# filterCard.net
KiCad netlist of a schematic drawn in EAGLE
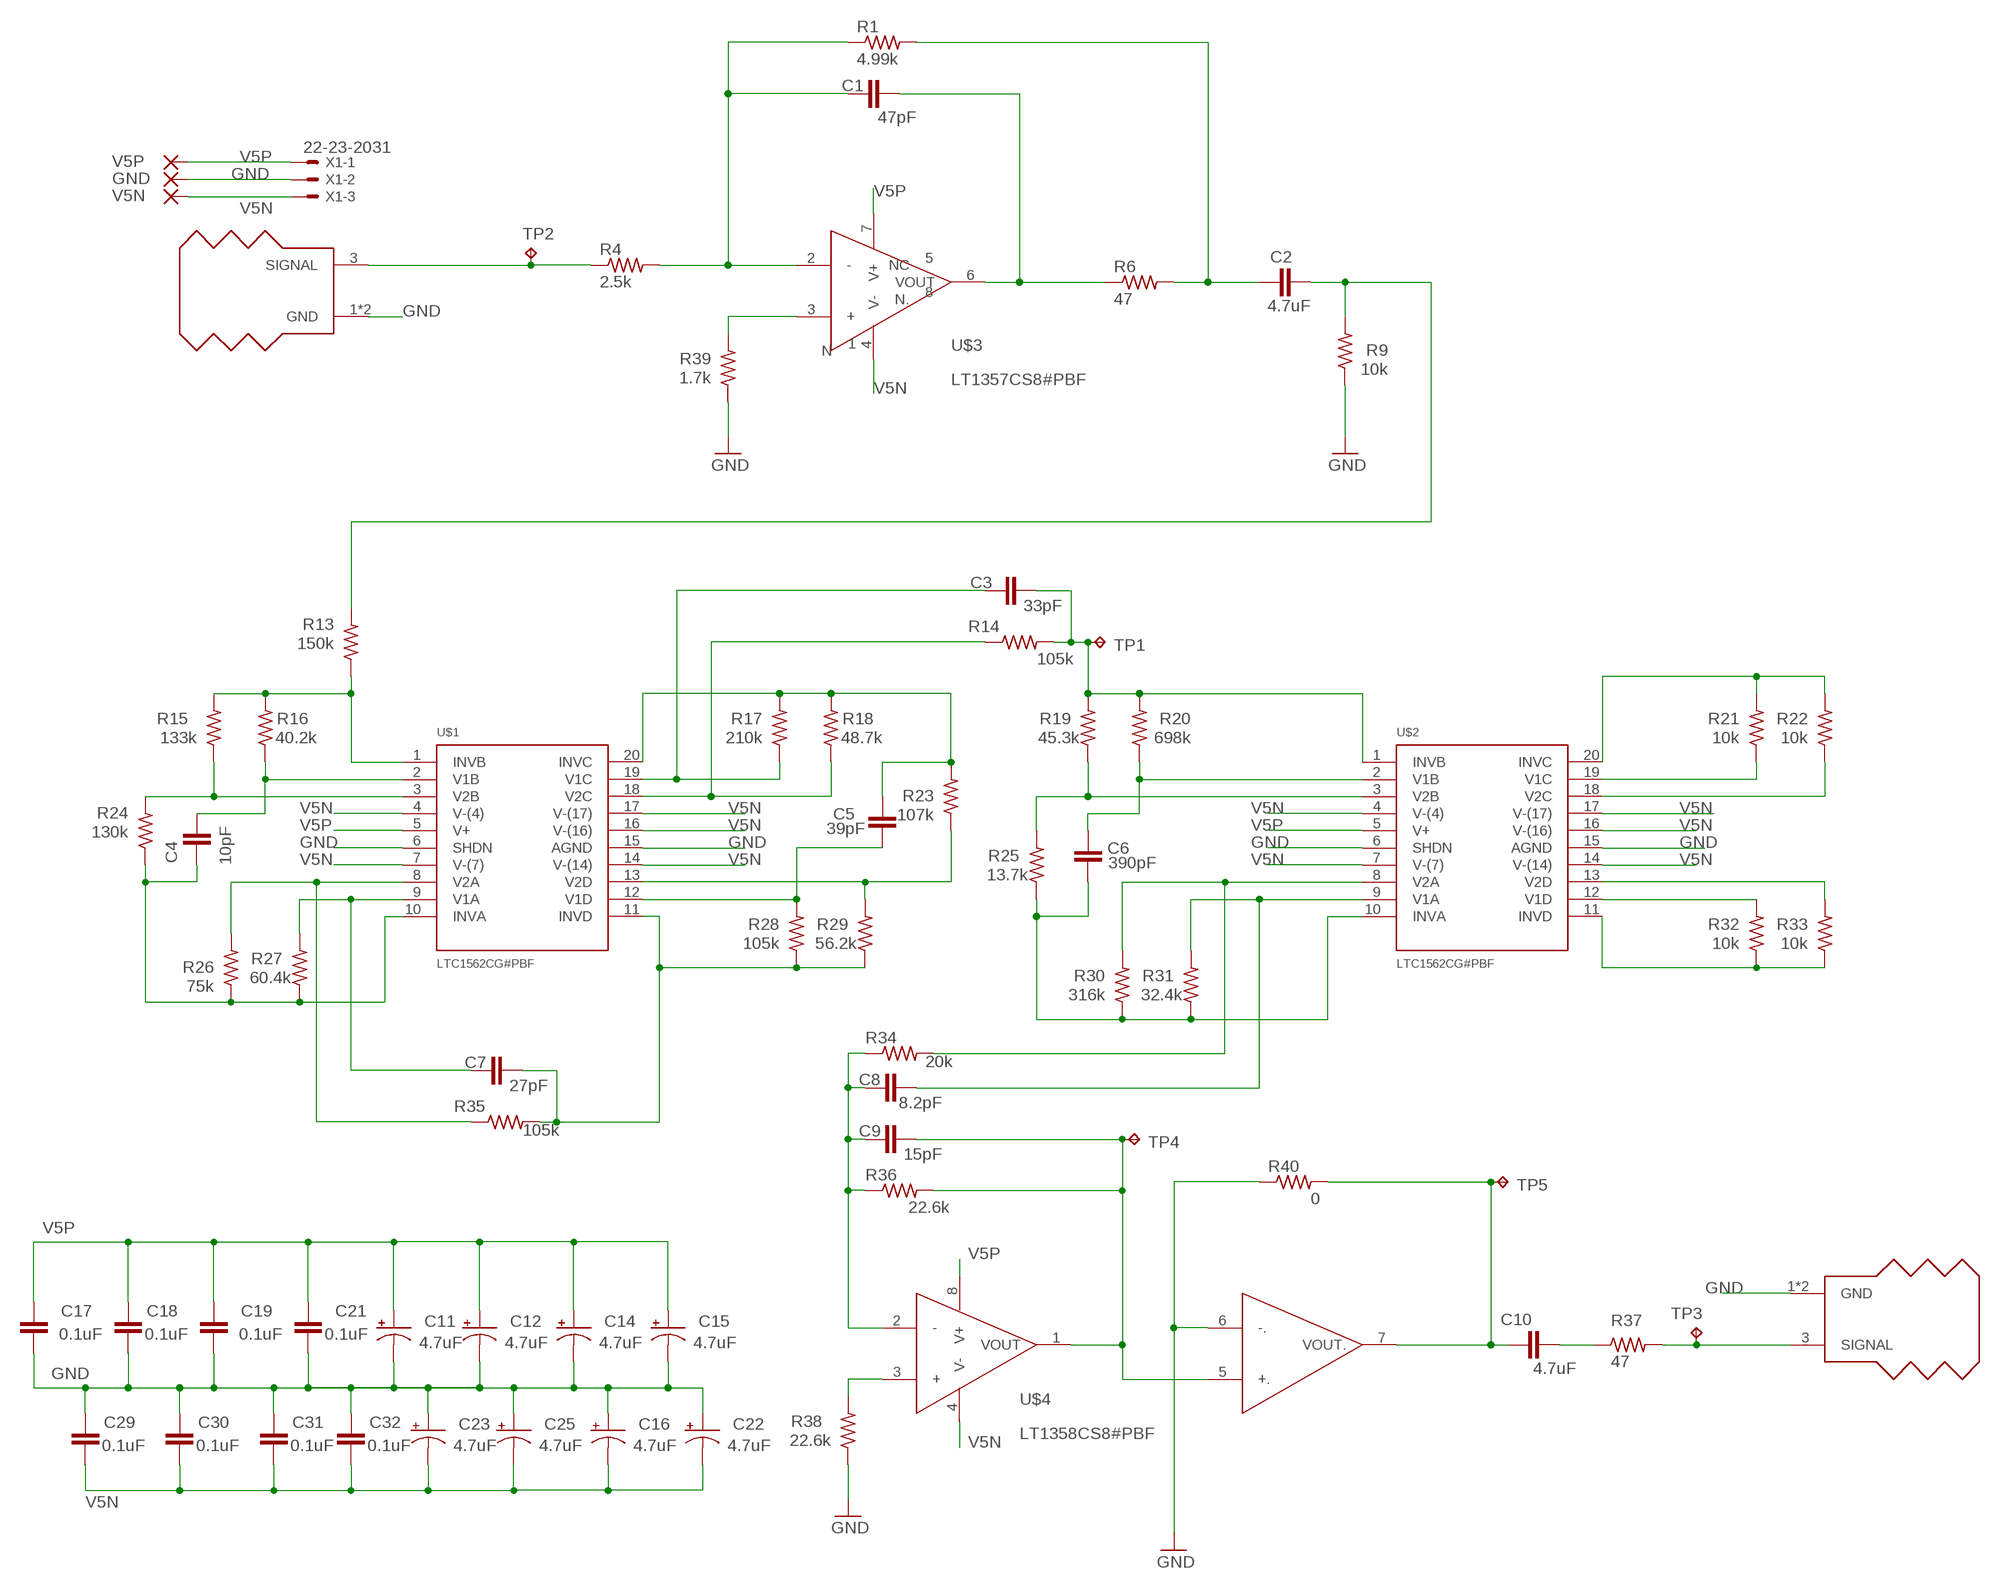
[diagram p0: schematic, sheet 1]

(export (version "E")
  (design (tool "Eeschema 10.0.6"))
  (components
    (comp (ref "C1")
      (value "47pF")
      (footprint "eagle-import:0603")
      (libsource (lib "eagle-import") (part "C0603"))
    )
    (comp (ref "C2")
      (value "4.7uF")
      (footprint "eagle-import:1206")
      (libsource (lib "eagle-import") (part "C1206"))
    )
    (comp (ref "C3")
      (value "33pF")
      (footprint "eagle-import:1206")
      (libsource (lib "eagle-import") (part "C1206"))
    )
    (comp (ref "C4")
      (value "10pF")
      (footprint "eagle-import:1206")
      (libsource (lib "eagle-import") (part "C1206"))
    )
    (comp (ref "C5")
      (value "39pF")
      (footprint "eagle-import:1206")
      (libsource (lib "eagle-import") (part "C1206"))
    )
    (comp (ref "C6")
      (value "390pF")
      (footprint "eagle-import:1206")
      (libsource (lib "eagle-import") (part "C1206"))
    )
    (comp (ref "C7")
      (value "27pF")
      (footprint "eagle-import:1206")
      (libsource (lib "eagle-import") (part "C1206"))
    )
    (comp (ref "C8")
      (value "8.2pF")
      (footprint "eagle-import:1206")
      (libsource (lib "eagle-import") (part "C1206"))
    )
    (comp (ref "C9")
      (value "15pF")
      (footprint "eagle-import:1206")
      (libsource (lib "eagle-import") (part "C1206"))
    )
    (comp (ref "C10")
      (value "4.7uF")
      (footprint "eagle-import:1206")
      (libsource (lib "eagle-import") (part "C1206"))
    )
    (comp (ref "C11")
      (value "4.7uF")
      (footprint "eagle-import:1206-POLAR")
      (libsource (lib "eagle-import") (part "C1206-POLAR"))
    )
    (comp (ref "C12")
      (value "4.7uF")
      (footprint "eagle-import:1206-POLAR")
      (libsource (lib "eagle-import") (part "C1206-POLAR"))
    )
    (comp (ref "C14")
      (value "4.7uF")
      (footprint "eagle-import:1206-POLAR")
      (libsource (lib "eagle-import") (part "C1206-POLAR"))
    )
    (comp (ref "C15")
      (value "4.7uF")
      (footprint "eagle-import:1206-POLAR")
      (libsource (lib "eagle-import") (part "C1206-POLAR"))
    )
    (comp (ref "C16")
      (value "4.7uF")
      (footprint "eagle-import:1206-POLAR")
      (libsource (lib "eagle-import") (part "C1206-POLAR"))
    )
    (comp (ref "C17")
      (value "0.1uF")
      (footprint "eagle-import:0603")
      (libsource (lib "eagle-import") (part "C0603"))
    )
    (comp (ref "C18")
      (value "0.1uF")
      (footprint "eagle-import:0603")
      (libsource (lib "eagle-import") (part "C0603"))
    )
    (comp (ref "C19")
      (value "0.1uF")
      (footprint "eagle-import:0603")
      (libsource (lib "eagle-import") (part "C0603"))
    )
    (comp (ref "C21")
      (value "0.1uF")
      (footprint "eagle-import:0603")
      (libsource (lib "eagle-import") (part "C0603"))
    )
    (comp (ref "C22")
      (value "4.7uF")
      (footprint "eagle-import:1206-POLAR")
      (libsource (lib "eagle-import") (part "C1206-POLAR"))
    )
    (comp (ref "C23")
      (value "4.7uF")
      (footprint "eagle-import:1206-POLAR")
      (libsource (lib "eagle-import") (part "C1206-POLAR"))
    )
    (comp (ref "C25")
      (value "4.7uF")
      (footprint "eagle-import:1206-POLAR")
      (libsource (lib "eagle-import") (part "C1206-POLAR"))
    )
    (comp (ref "C29")
      (value "0.1uF")
      (footprint "eagle-import:0603")
      (libsource (lib "eagle-import") (part "C0603"))
    )
    (comp (ref "C30")
      (value "0.1uF")
      (footprint "eagle-import:0603")
      (libsource (lib "eagle-import") (part "C0603"))
    )
    (comp (ref "C31")
      (value "0.1uF")
      (footprint "eagle-import:0603")
      (libsource (lib "eagle-import") (part "C0603"))
    )
    (comp (ref "C32")
      (value "0.1uF")
      (footprint "eagle-import:0603")
      (libsource (lib "eagle-import") (part "C0603"))
    )
    (comp (ref "GND")
      (value "ground")
      (footprint "eagle-import:2,54_0,8")
      (libsource (lib "eagle-import") (part "2,54/0,8"))
    )
    (comp (ref "R1")
      (value "4.99k")
      (footprint "eagle-import:R0603")
      (libsource (lib "eagle-import") (part "resistor_R-US_R0603"))
    )
    (comp (ref "R4")
      (value "2.5k")
      (footprint "eagle-import:R0603")
      (libsource (lib "eagle-import") (part "resistor_R-US_R0603"))
    )
    (comp (ref "R6")
      (value "47")
      (footprint "eagle-import:R1206")
      (libsource (lib "eagle-import") (part "resistor_R-US_R1206"))
    )
    (comp (ref "R9")
      (value "10k")
      (footprint "eagle-import:R1206")
      (libsource (lib "eagle-import") (part "resistor_R-US_R1206"))
    )
    (comp (ref "R13")
      (value "150k")
      (footprint "eagle-import:R1206")
      (libsource (lib "eagle-import") (part "resistor_R-US_R1206"))
    )
    (comp (ref "R14")
      (value "105k")
      (footprint "eagle-import:R1206")
      (libsource (lib "eagle-import") (part "resistor_R-US_R1206"))
    )
    (comp (ref "R15")
      (value "133k")
      (footprint "eagle-import:R1206")
      (libsource (lib "eagle-import") (part "resistor_R-US_R1206"))
    )
    (comp (ref "R16")
      (value "40.2k")
      (footprint "eagle-import:R1206")
      (libsource (lib "eagle-import") (part "resistor_R-US_R1206"))
    )
    (comp (ref "R17")
      (value "210k")
      (footprint "eagle-import:R1206")
      (libsource (lib "eagle-import") (part "resistor_R-US_R1206"))
    )
    (comp (ref "R18")
      (value "48.7k")
      (footprint "eagle-import:R1206")
      (libsource (lib "eagle-import") (part "resistor_R-US_R1206"))
    )
    (comp (ref "R19")
      (value "45.3k")
      (footprint "eagle-import:R1206")
      (libsource (lib "eagle-import") (part "resistor_R-US_R1206"))
    )
    (comp (ref "R20")
      (value "698k")
      (footprint "eagle-import:R1206")
      (libsource (lib "eagle-import") (part "resistor_R-US_R1206"))
    )
    (comp (ref "R21")
      (value "10k")
      (footprint "eagle-import:R1206")
      (libsource (lib "eagle-import") (part "resistor_R-US_R1206"))
    )
    (comp (ref "R22")
      (value "10k")
      (footprint "eagle-import:R1206")
      (libsource (lib "eagle-import") (part "resistor_R-US_R1206"))
    )
    (comp (ref "R23")
      (value "107k")
      (footprint "eagle-import:R1206")
      (libsource (lib "eagle-import") (part "R-US_R1206"))
    )
    (comp (ref "R24")
      (value "130k")
      (footprint "eagle-import:R1206")
      (libsource (lib "eagle-import") (part "R-US_R1206"))
    )
    (comp (ref "R25")
      (value "13.7k")
      (footprint "eagle-import:R1206")
      (libsource (lib "eagle-import") (part "R-US_R1206"))
    )
    (comp (ref "R26")
      (value "75k")
      (footprint "eagle-import:R1206")
      (libsource (lib "eagle-import") (part "R-US_R1206"))
    )
    (comp (ref "R27")
      (value "60.4k")
      (footprint "eagle-import:R1206")
      (libsource (lib "eagle-import") (part "R-US_R1206"))
    )
    (comp (ref "R28")
      (value "105k")
      (footprint "eagle-import:R1206")
      (libsource (lib "eagle-import") (part "resistor_R-US_R1206"))
    )
    (comp (ref "R29")
      (value "56.2k")
      (footprint "eagle-import:R1206")
      (libsource (lib "eagle-import") (part "R-US_R1206"))
    )
    (comp (ref "R30")
      (value "316k")
      (footprint "eagle-import:R1206")
      (libsource (lib "eagle-import") (part "R-US_R1206"))
    )
    (comp (ref "R31")
      (value "32.4k")
      (footprint "eagle-import:R1206")
      (libsource (lib "eagle-import") (part "R-US_R1206"))
    )
    (comp (ref "R32")
      (value "10k")
      (footprint "eagle-import:R1206")
      (libsource (lib "eagle-import") (part "resistor_R-US_R1206"))
    )
    (comp (ref "R33")
      (value "10k")
      (footprint "eagle-import:R1206")
      (libsource (lib "eagle-import") (part "resistor_R-US_R1206"))
    )
    (comp (ref "R34")
      (value "20k")
      (footprint "eagle-import:R1206")
      (libsource (lib "eagle-import") (part "R-US_R1206"))
    )
    (comp (ref "R35")
      (value "105k")
      (footprint "eagle-import:R1206")
      (libsource (lib "eagle-import") (part "resistor_R-US_R1206"))
    )
    (comp (ref "R36")
      (value "22.6k")
      (footprint "eagle-import:R1206")
      (libsource (lib "eagle-import") (part "R-US_R1206"))
    )
    (comp (ref "R37")
      (value "47")
      (footprint "eagle-import:R1206")
      (libsource (lib "eagle-import") (part "resistor_R-US_R1206"))
    )
    (comp (ref "R38")
      (value "22.6k")
      (footprint "eagle-import:R1206")
      (libsource (lib "eagle-import") (part "resistor_R-US_R1206"))
    )
    (comp (ref "R39")
      (value "1.7k")
      (footprint "eagle-import:R0603")
      (libsource (lib "eagle-import") (part "resistor_R-US_R0603"))
    )
    (comp (ref "R40")
      (value "0")
      (footprint "eagle-import:R0805")
      (libsource (lib "eagle-import") (part "resistor_R-US_R0805"))
    )
    (comp (ref "TP1")
      (value "TPPAD1-17")
      (footprint "eagle-import:P1-17")
      (libsource (lib "eagle-import") (part "TPPAD1-17"))
    )
    (comp (ref "TP2")
      (value "TPPAD1-13")
      (footprint "eagle-import:P1-13")
      (libsource (lib "eagle-import") (part "TPPAD1-13"))
    )
    (comp (ref "TP3")
      (value "TPPAD1-13")
      (footprint "eagle-import:P1-13")
      (libsource (lib "eagle-import") (part "TPPAD1-13"))
    )
    (comp (ref "TP4")
      (value "TPPAD1-17")
      (footprint "eagle-import:P1-17")
      (libsource (lib "eagle-import") (part "TPPAD1-17"))
    )
    (comp (ref "TP5")
      (value "TPPAD1-17")
      (footprint "eagle-import:P1-17")
      (libsource (lib "eagle-import") (part "TPPAD1-17"))
    )
    (comp (ref "U$1")
      (value "LTC1562CG#PBF")
      (footprint "eagle-import:TSSOP20")
      (libsource (lib "eagle-import") (part "LTC1562CG#PBF"))
    )
    (comp (ref "U$2")
      (value "LTC1562CG#PBF")
      (footprint "eagle-import:TSSOP20")
      (libsource (lib "eagle-import") (part "LTC1562CG#PBF"))
    )
    (comp (ref "U$3")
      (value "LT1357CS8#PBF")
      (footprint "eagle-import:8-SOIC")
      (libsource (lib "eagle-import") (part "LT1357CS8#PBF"))
    )
    (comp (ref "U$4")
      (value "LT1358CS8#PBF")
      (footprint "eagle-import:8-SOIC")
      (libsource (lib "eagle-import") (part "LT1358CS8#PBF"))
    )
    (comp (ref "U$5")
      (value "MY_SMASMD")
      (footprint "eagle-import:MY_SMA")
      (libsource (lib "eagle-import") (part "MY_SMASMD"))
    )
    (comp (ref "U$6")
      (value "MY_SMASMD")
      (footprint "eagle-import:MY_SMA")
      (libsource (lib "eagle-import") (part "MY_SMASMD"))
    )
    (comp (ref "V5N")
      (value "-5")
      (footprint "eagle-import:2,54_0,8")
      (libsource (lib "eagle-import") (part "2,54/0,8"))
    )
    (comp (ref "V5P")
      (value "5")
      (footprint "eagle-import:2,54_0,8")
      (libsource (lib "eagle-import") (part "2,54/0,8"))
    )
    (comp (ref "X1")
      (value "22-23-2031")
      (footprint "eagle-import:22-23-2031")
      (fields (field (name "MF") "MOLEX"))
      (libsource (lib "eagle-import") (part "22-23-2031"))
    )
  )
  (nets
    (net (code "1") (name "/V5N") (class "Default")
      (node (ref "C16") (pin "-") (pinfunction "-_-") (pintype "passive"))
      (node (ref "C22") (pin "-") (pinfunction "-_-") (pintype "passive"))
      (node (ref "C23") (pin "-") (pinfunction "-_-") (pintype "passive"))
      (node (ref "C25") (pin "-") (pinfunction "-_-") (pintype "passive"))
      (node (ref "C29") (pin "2") (pinfunction "2_2") (pintype "passive"))
      (node (ref "C30") (pin "2") (pinfunction "2_2") (pintype "passive"))
      (node (ref "C31") (pin "2") (pinfunction "2_2") (pintype "passive"))
      (node (ref "C32") (pin "2") (pinfunction "2_2") (pintype "passive"))
      (node (ref "U$1") (pin "14") (pinfunction "V-(14)_14") (pintype "bidirectional"))
      (node (ref "U$1") (pin "16") (pinfunction "V-(16)_16") (pintype "bidirectional"))
      (node (ref "U$1") (pin "17") (pinfunction "V-(17)_17") (pintype "bidirectional"))
      (node (ref "U$1") (pin "4") (pinfunction "V-(4)_4") (pintype "bidirectional"))
      (node (ref "U$1") (pin "7") (pinfunction "V-(7)_7") (pintype "bidirectional"))
      (node (ref "U$2") (pin "14") (pinfunction "V-(14)_14") (pintype "bidirectional"))
      (node (ref "U$2") (pin "16") (pinfunction "V-(16)_16") (pintype "bidirectional"))
      (node (ref "U$2") (pin "17") (pinfunction "V-(17)_17") (pintype "bidirectional"))
      (node (ref "U$2") (pin "4") (pinfunction "V-(4)_4") (pintype "bidirectional"))
      (node (ref "U$2") (pin "7") (pinfunction "V-(7)_7") (pintype "bidirectional"))
      (node (ref "U$3") (pin "4") (pinfunction "V-_4") (pintype "bidirectional"))
      (node (ref "U$4") (pin "4") (pinfunction "V-_4") (pintype "bidirectional"))
      (node (ref "V5N") (pin "1") (pinfunction "P_1") (pintype "passive"))
      (node (ref "X1") (pin "3") (pinfunction "S_3") (pintype "passive"))
    )
    (net (code "2") (name "/V5P") (class "Default")
      (node (ref "C11") (pin "+") (pinfunction "+_+") (pintype "passive"))
      (node (ref "C12") (pin "+") (pinfunction "+_+") (pintype "passive"))
      (node (ref "C14") (pin "+") (pinfunction "+_+") (pintype "passive"))
      (node (ref "C15") (pin "+") (pinfunction "+_+") (pintype "passive"))
      (node (ref "C17") (pin "1") (pinfunction "1_1") (pintype "passive"))
      (node (ref "C18") (pin "1") (pinfunction "1_1") (pintype "passive"))
      (node (ref "C19") (pin "1") (pinfunction "1_1") (pintype "passive"))
      (node (ref "C21") (pin "1") (pinfunction "1_1") (pintype "passive"))
      (node (ref "U$1") (pin "5") (pinfunction "V+_5") (pintype "bidirectional"))
      (node (ref "U$2") (pin "5") (pinfunction "V+_5") (pintype "bidirectional"))
      (node (ref "U$3") (pin "7") (pinfunction "V+_7") (pintype "bidirectional"))
      (node (ref "U$4") (pin "8") (pinfunction "V+_8") (pintype "bidirectional"))
      (node (ref "V5P") (pin "1") (pinfunction "P_1") (pintype "passive"))
      (node (ref "X1") (pin "1") (pinfunction "S_1") (pintype "passive"))
    )
    (net (code "3") (name "GND") (class "Default")
      (node (ref "C11") (pin "-") (pinfunction "-_-") (pintype "passive"))
      (node (ref "C12") (pin "-") (pinfunction "-_-") (pintype "passive"))
      (node (ref "C14") (pin "-") (pinfunction "-_-") (pintype "passive"))
      (node (ref "C15") (pin "-") (pinfunction "-_-") (pintype "passive"))
      (node (ref "C16") (pin "+") (pinfunction "+_+") (pintype "passive"))
      (node (ref "C17") (pin "2") (pinfunction "2_2") (pintype "passive"))
      (node (ref "C18") (pin "2") (pinfunction "2_2") (pintype "passive"))
      (node (ref "C19") (pin "2") (pinfunction "2_2") (pintype "passive"))
      (node (ref "C21") (pin "2") (pinfunction "2_2") (pintype "passive"))
      (node (ref "C22") (pin "+") (pinfunction "+_+") (pintype "passive"))
      (node (ref "C23") (pin "+") (pinfunction "+_+") (pintype "passive"))
      (node (ref "C25") (pin "+") (pinfunction "+_+") (pintype "passive"))
      (node (ref "C29") (pin "1") (pinfunction "1_1") (pintype "passive"))
      (node (ref "C30") (pin "1") (pinfunction "1_1") (pintype "passive"))
      (node (ref "C31") (pin "1") (pinfunction "1_1") (pintype "passive"))
      (node (ref "C32") (pin "1") (pinfunction "1_1") (pintype "passive"))
      (node (ref "GND") (pin "1") (pinfunction "P_1") (pintype "passive"))
      (node (ref "R38") (pin "1") (pinfunction "1_1") (pintype "passive"))
      (node (ref "R39") (pin "1") (pinfunction "1_1") (pintype "passive"))
      (node (ref "R40") (pin "1") (pinfunction "1_1") (pintype "passive"))
      (node (ref "R9") (pin "1") (pinfunction "1_1") (pintype "passive"))
      (node (ref "U$1") (pin "15") (pinfunction "AGND_15") (pintype "bidirectional"))
      (node (ref "U$1") (pin "6") (pinfunction "SHDN_6") (pintype "bidirectional"))
      (node (ref "U$2") (pin "15") (pinfunction "AGND_15") (pintype "bidirectional"))
      (node (ref "U$2") (pin "6") (pinfunction "SHDN_6") (pintype "bidirectional"))
      (node (ref "U$4") (pin "6") (pinfunction "-._6") (pintype "bidirectional"))
      (node (ref "U$5") (pin "1") (pinfunction "GND_1") (pintype "bidirectional"))
      (node (ref "U$5") (pin "2") (pinfunction "GND_2") (pintype "bidirectional"))
      (node (ref "U$6") (pin "1") (pinfunction "GND_1") (pintype "bidirectional"))
      (node (ref "U$6") (pin "2") (pinfunction "GND_2") (pintype "bidirectional"))
      (node (ref "X1") (pin "2") (pinfunction "S_2") (pintype "passive"))
    )
    (net (code "4") (name "Net-(C2-Pad1)") (class "Default")
      (node (ref "C2") (pin "1") (pinfunction "1_1") (pintype "passive"))
      (node (ref "R1") (pin "2") (pinfunction "2_2") (pintype "passive"))
      (node (ref "R6") (pin "2") (pinfunction "2_2") (pintype "passive"))
    )
    (net (code "5") (name "Net-(C2-Pad2)") (class "Default")
      (node (ref "C2") (pin "2") (pinfunction "2_2") (pintype "passive"))
      (node (ref "R13") (pin "2") (pinfunction "2_2") (pintype "passive"))
      (node (ref "R9") (pin "2") (pinfunction "2_2") (pintype "passive"))
    )
    (net (code "6") (name "Net-(C10-Pad2)") (class "Default")
      (node (ref "C10") (pin "2") (pinfunction "2_2") (pintype "passive"))
      (node (ref "R37") (pin "1") (pinfunction "1_1") (pintype "passive"))
    )
    (net (code "7") (name "Net-(U$1-INVA)") (class "Default")
      (node (ref "C4") (pin "2") (pinfunction "2_2") (pintype "passive"))
      (node (ref "R24") (pin "1") (pinfunction "1_1") (pintype "passive"))
      (node (ref "R26") (pin "1") (pinfunction "1_1") (pintype "passive"))
      (node (ref "R27") (pin "1") (pinfunction "1_1") (pintype "passive"))
      (node (ref "U$1") (pin "10") (pinfunction "INVA_10") (pintype "bidirectional"))
    )
    (net (code "8") (name "Net-(U$1-INVB)") (class "Default")
      (node (ref "R13") (pin "1") (pinfunction "1_1") (pintype "passive"))
      (node (ref "R15") (pin "2") (pinfunction "2_2") (pintype "passive"))
      (node (ref "R16") (pin "2") (pinfunction "2_2") (pintype "passive"))
      (node (ref "U$1") (pin "1") (pinfunction "INVB_1") (pintype "bidirectional"))
    )
    (net (code "9") (name "Net-(U$1-INVC)") (class "Default")
      (node (ref "C5") (pin "1") (pinfunction "1_1") (pintype "passive"))
      (node (ref "R17") (pin "2") (pinfunction "2_2") (pintype "passive"))
      (node (ref "R18") (pin "2") (pinfunction "2_2") (pintype "passive"))
      (node (ref "R23") (pin "2") (pinfunction "2_2") (pintype "passive"))
      (node (ref "U$1") (pin "20") (pinfunction "INVC_20") (pintype "bidirectional"))
    )
    (net (code "10") (name "Net-(U$1-INVD)") (class "Default")
      (node (ref "C7") (pin "2") (pinfunction "2_2") (pintype "passive"))
      (node (ref "R28") (pin "1") (pinfunction "1_1") (pintype "passive"))
      (node (ref "R29") (pin "1") (pinfunction "1_1") (pintype "passive"))
      (node (ref "R35") (pin "2") (pinfunction "2_2") (pintype "passive"))
      (node (ref "U$1") (pin "11") (pinfunction "INVD_11") (pintype "bidirectional"))
    )
    (net (code "11") (name "Net-(U$1-V1A)") (class "Default")
      (node (ref "C7") (pin "1") (pinfunction "1_1") (pintype "passive"))
      (node (ref "R27") (pin "2") (pinfunction "2_2") (pintype "passive"))
      (node (ref "U$1") (pin "9") (pinfunction "V1A_9") (pintype "bidirectional"))
    )
    (net (code "12") (name "Net-(U$1-V1B)") (class "Default")
      (node (ref "C4") (pin "1") (pinfunction "1_1") (pintype "passive"))
      (node (ref "R16") (pin "1") (pinfunction "1_1") (pintype "passive"))
      (node (ref "U$1") (pin "2") (pinfunction "V1B_2") (pintype "bidirectional"))
    )
    (net (code "13") (name "Net-(U$1-V1C)") (class "Default")
      (node (ref "C3") (pin "1") (pinfunction "1_1") (pintype "passive"))
      (node (ref "R17") (pin "1") (pinfunction "1_1") (pintype "passive"))
      (node (ref "U$1") (pin "19") (pinfunction "V1C_19") (pintype "bidirectional"))
    )
    (net (code "14") (name "Net-(U$1-V1D)") (class "Default")
      (node (ref "C5") (pin "2") (pinfunction "2_2") (pintype "passive"))
      (node (ref "R28") (pin "2") (pinfunction "2_2") (pintype "passive"))
      (node (ref "U$1") (pin "12") (pinfunction "V1D_12") (pintype "bidirectional"))
    )
    (net (code "15") (name "Net-(U$1-V2A)") (class "Default")
      (node (ref "R26") (pin "2") (pinfunction "2_2") (pintype "passive"))
      (node (ref "R35") (pin "1") (pinfunction "1_1") (pintype "passive"))
      (node (ref "U$1") (pin "8") (pinfunction "V2A_8") (pintype "bidirectional"))
    )
    (net (code "16") (name "Net-(U$1-V2B)") (class "Default")
      (node (ref "R15") (pin "1") (pinfunction "1_1") (pintype "passive"))
      (node (ref "R24") (pin "2") (pinfunction "2_2") (pintype "passive"))
      (node (ref "U$1") (pin "3") (pinfunction "V2B_3") (pintype "bidirectional"))
    )
    (net (code "17") (name "Net-(U$1-V2C)") (class "Default")
      (node (ref "R14") (pin "1") (pinfunction "1_1") (pintype "passive"))
      (node (ref "R18") (pin "1") (pinfunction "1_1") (pintype "passive"))
      (node (ref "U$1") (pin "18") (pinfunction "V2C_18") (pintype "bidirectional"))
    )
    (net (code "18") (name "Net-(U$1-V2D)") (class "Default")
      (node (ref "R23") (pin "1") (pinfunction "1_1") (pintype "passive"))
      (node (ref "R29") (pin "2") (pinfunction "2_2") (pintype "passive"))
      (node (ref "U$1") (pin "13") (pinfunction "V2D_13") (pintype "bidirectional"))
    )
    (net (code "19") (name "Net-(U$2-INVA)") (class "Default")
      (node (ref "C6") (pin "2") (pinfunction "2_2") (pintype "passive"))
      (node (ref "R25") (pin "1") (pinfunction "1_1") (pintype "passive"))
      (node (ref "R30") (pin "1") (pinfunction "1_1") (pintype "passive"))
      (node (ref "R31") (pin "1") (pinfunction "1_1") (pintype "passive"))
      (node (ref "U$2") (pin "10") (pinfunction "INVA_10") (pintype "bidirectional"))
    )
    (net (code "20") (name "Net-(U$2-INVB)") (class "Default")
      (node (ref "C3") (pin "2") (pinfunction "2_2") (pintype "passive"))
      (node (ref "R14") (pin "2") (pinfunction "2_2") (pintype "passive"))
      (node (ref "R19") (pin "2") (pinfunction "2_2") (pintype "passive"))
      (node (ref "R20") (pin "2") (pinfunction "2_2") (pintype "passive"))
      (node (ref "TP1") (pin "TP") (pinfunction "TP_TP") (pintype "input"))
      (node (ref "U$2") (pin "1") (pinfunction "INVB_1") (pintype "bidirectional"))
    )
    (net (code "21") (name "Net-(U$2-INVC)") (class "Default")
      (node (ref "R21") (pin "2") (pinfunction "2_2") (pintype "passive"))
      (node (ref "R22") (pin "2") (pinfunction "2_2") (pintype "passive"))
      (node (ref "U$2") (pin "20") (pinfunction "INVC_20") (pintype "bidirectional"))
    )
    (net (code "22") (name "Net-(U$2-INVD)") (class "Default")
      (node (ref "R32") (pin "1") (pinfunction "1_1") (pintype "passive"))
      (node (ref "R33") (pin "1") (pinfunction "1_1") (pintype "passive"))
      (node (ref "U$2") (pin "11") (pinfunction "INVD_11") (pintype "bidirectional"))
    )
    (net (code "23") (name "Net-(U$2-V1A)") (class "Default")
      (node (ref "C8") (pin "2") (pinfunction "2_2") (pintype "passive"))
      (node (ref "R31") (pin "2") (pinfunction "2_2") (pintype "passive"))
      (node (ref "U$2") (pin "9") (pinfunction "V1A_9") (pintype "bidirectional"))
    )
    (net (code "24") (name "Net-(U$2-V1B)") (class "Default")
      (node (ref "C6") (pin "1") (pinfunction "1_1") (pintype "passive"))
      (node (ref "R20") (pin "1") (pinfunction "1_1") (pintype "passive"))
      (node (ref "U$2") (pin "2") (pinfunction "V1B_2") (pintype "bidirectional"))
    )
    (net (code "25") (name "Net-(U$2-V1C)") (class "Default")
      (node (ref "R21") (pin "1") (pinfunction "1_1") (pintype "passive"))
      (node (ref "U$2") (pin "19") (pinfunction "V1C_19") (pintype "bidirectional"))
    )
    (net (code "26") (name "Net-(U$2-V1D)") (class "Default")
      (node (ref "R32") (pin "2") (pinfunction "2_2") (pintype "passive"))
      (node (ref "U$2") (pin "12") (pinfunction "V1D_12") (pintype "bidirectional"))
    )
    (net (code "27") (name "Net-(U$2-V2A)") (class "Default")
      (node (ref "R30") (pin "2") (pinfunction "2_2") (pintype "passive"))
      (node (ref "R34") (pin "2") (pinfunction "2_2") (pintype "passive"))
      (node (ref "U$2") (pin "8") (pinfunction "V2A_8") (pintype "bidirectional"))
    )
    (net (code "28") (name "Net-(U$2-V2B)") (class "Default")
      (node (ref "R19") (pin "1") (pinfunction "1_1") (pintype "passive"))
      (node (ref "R25") (pin "2") (pinfunction "2_2") (pintype "passive"))
      (node (ref "U$2") (pin "3") (pinfunction "V2B_3") (pintype "bidirectional"))
    )
    (net (code "29") (name "Net-(U$2-V2C)") (class "Default")
      (node (ref "R22") (pin "1") (pinfunction "1_1") (pintype "passive"))
      (node (ref "U$2") (pin "18") (pinfunction "V2C_18") (pintype "bidirectional"))
    )
    (net (code "30") (name "Net-(U$2-V2D)") (class "Default")
      (node (ref "R33") (pin "2") (pinfunction "2_2") (pintype "passive"))
      (node (ref "U$2") (pin "13") (pinfunction "V2D_13") (pintype "bidirectional"))
    )
    (net (code "31") (name "Net-(U$3-+)") (class "Default")
      (node (ref "R39") (pin "2") (pinfunction "2_2") (pintype "passive"))
      (node (ref "U$3") (pin "3") (pinfunction "+_3") (pintype "bidirectional"))
    )
    (net (code "32") (name "Net-(U$3--)") (class "Default")
      (node (ref "C1") (pin "1") (pinfunction "1_1") (pintype "passive"))
      (node (ref "R1") (pin "1") (pinfunction "1_1") (pintype "passive"))
      (node (ref "R4") (pin "2") (pinfunction "2_2") (pintype "passive"))
      (node (ref "U$3") (pin "2") (pinfunction "-_2") (pintype "bidirectional"))
    )
    (net (code "33") (name "Net-(U$3-VOUT)") (class "Default")
      (node (ref "C1") (pin "2") (pinfunction "2_2") (pintype "passive"))
      (node (ref "R6") (pin "1") (pinfunction "1_1") (pintype "passive"))
      (node (ref "U$3") (pin "6") (pinfunction "VOUT_6") (pintype "bidirectional"))
    )
    (net (code "34") (name "Net-(U$4-+)") (class "Default")
      (node (ref "R38") (pin "2") (pinfunction "2_2") (pintype "passive"))
      (node (ref "U$4") (pin "3") (pinfunction "+_3") (pintype "bidirectional"))
    )
    (net (code "35") (name "Net-(U$4-+.)") (class "Default")
      (node (ref "C9") (pin "2") (pinfunction "2_2") (pintype "passive"))
      (node (ref "R36") (pin "2") (pinfunction "2_2") (pintype "passive"))
      (node (ref "TP4") (pin "TP") (pinfunction "TP_TP") (pintype "input"))
      (node (ref "U$4") (pin "1") (pinfunction "VOUT_1") (pintype "bidirectional"))
      (node (ref "U$4") (pin "5") (pinfunction "+._5") (pintype "bidirectional"))
    )
    (net (code "36") (name "Net-(U$4--)") (class "Default")
      (node (ref "C8") (pin "1") (pinfunction "1_1") (pintype "passive"))
      (node (ref "C9") (pin "1") (pinfunction "1_1") (pintype "passive"))
      (node (ref "R34") (pin "1") (pinfunction "1_1") (pintype "passive"))
      (node (ref "R36") (pin "1") (pinfunction "1_1") (pintype "passive"))
      (node (ref "U$4") (pin "2") (pinfunction "-_2") (pintype "bidirectional"))
    )
    (net (code "37") (name "Net-(U$4-VOUT.)") (class "Default")
      (node (ref "C10") (pin "1") (pinfunction "1_1") (pintype "passive"))
      (node (ref "R40") (pin "2") (pinfunction "2_2") (pintype "passive"))
      (node (ref "TP5") (pin "TP") (pinfunction "TP_TP") (pintype "input"))
      (node (ref "U$4") (pin "7") (pinfunction "VOUT._7") (pintype "bidirectional"))
    )
    (net (code "38") (name "Net-(U$5-SIGNAL)") (class "Default")
      (node (ref "R4") (pin "1") (pinfunction "1_1") (pintype "passive"))
      (node (ref "TP2") (pin "TP") (pinfunction "TP_TP") (pintype "input"))
      (node (ref "U$5") (pin "3") (pinfunction "SIGNAL_3") (pintype "bidirectional"))
    )
    (net (code "39") (name "Net-(U$6-SIGNAL)") (class "Default")
      (node (ref "R37") (pin "2") (pinfunction "2_2") (pintype "passive"))
      (node (ref "TP3") (pin "TP") (pinfunction "TP_TP") (pintype "input"))
      (node (ref "U$6") (pin "3") (pinfunction "SIGNAL_3") (pintype "bidirectional"))
    )
    (net (code "40") (name "unconnected-(U$3-N-Pad1)") (class "Default")
      (node (ref "U$3") (pin "1") (pinfunction "N_1") (pintype "bidirectional"))
    )
    (net (code "41") (name "unconnected-(U$3-N.-Pad8)") (class "Default")
      (node (ref "U$3") (pin "8") (pinfunction "N._8") (pintype "bidirectional"))
    )
    (net (code "42") (name "unconnected-(U$3-NC-Pad5)") (class "Default")
      (node (ref "U$3") (pin "5") (pinfunction "NC_5") (pintype "bidirectional"))
    )
  )
)
